# imx6_ctrl_i2c1.net
KiCad netlist of a schematic drawn in Altium Designer
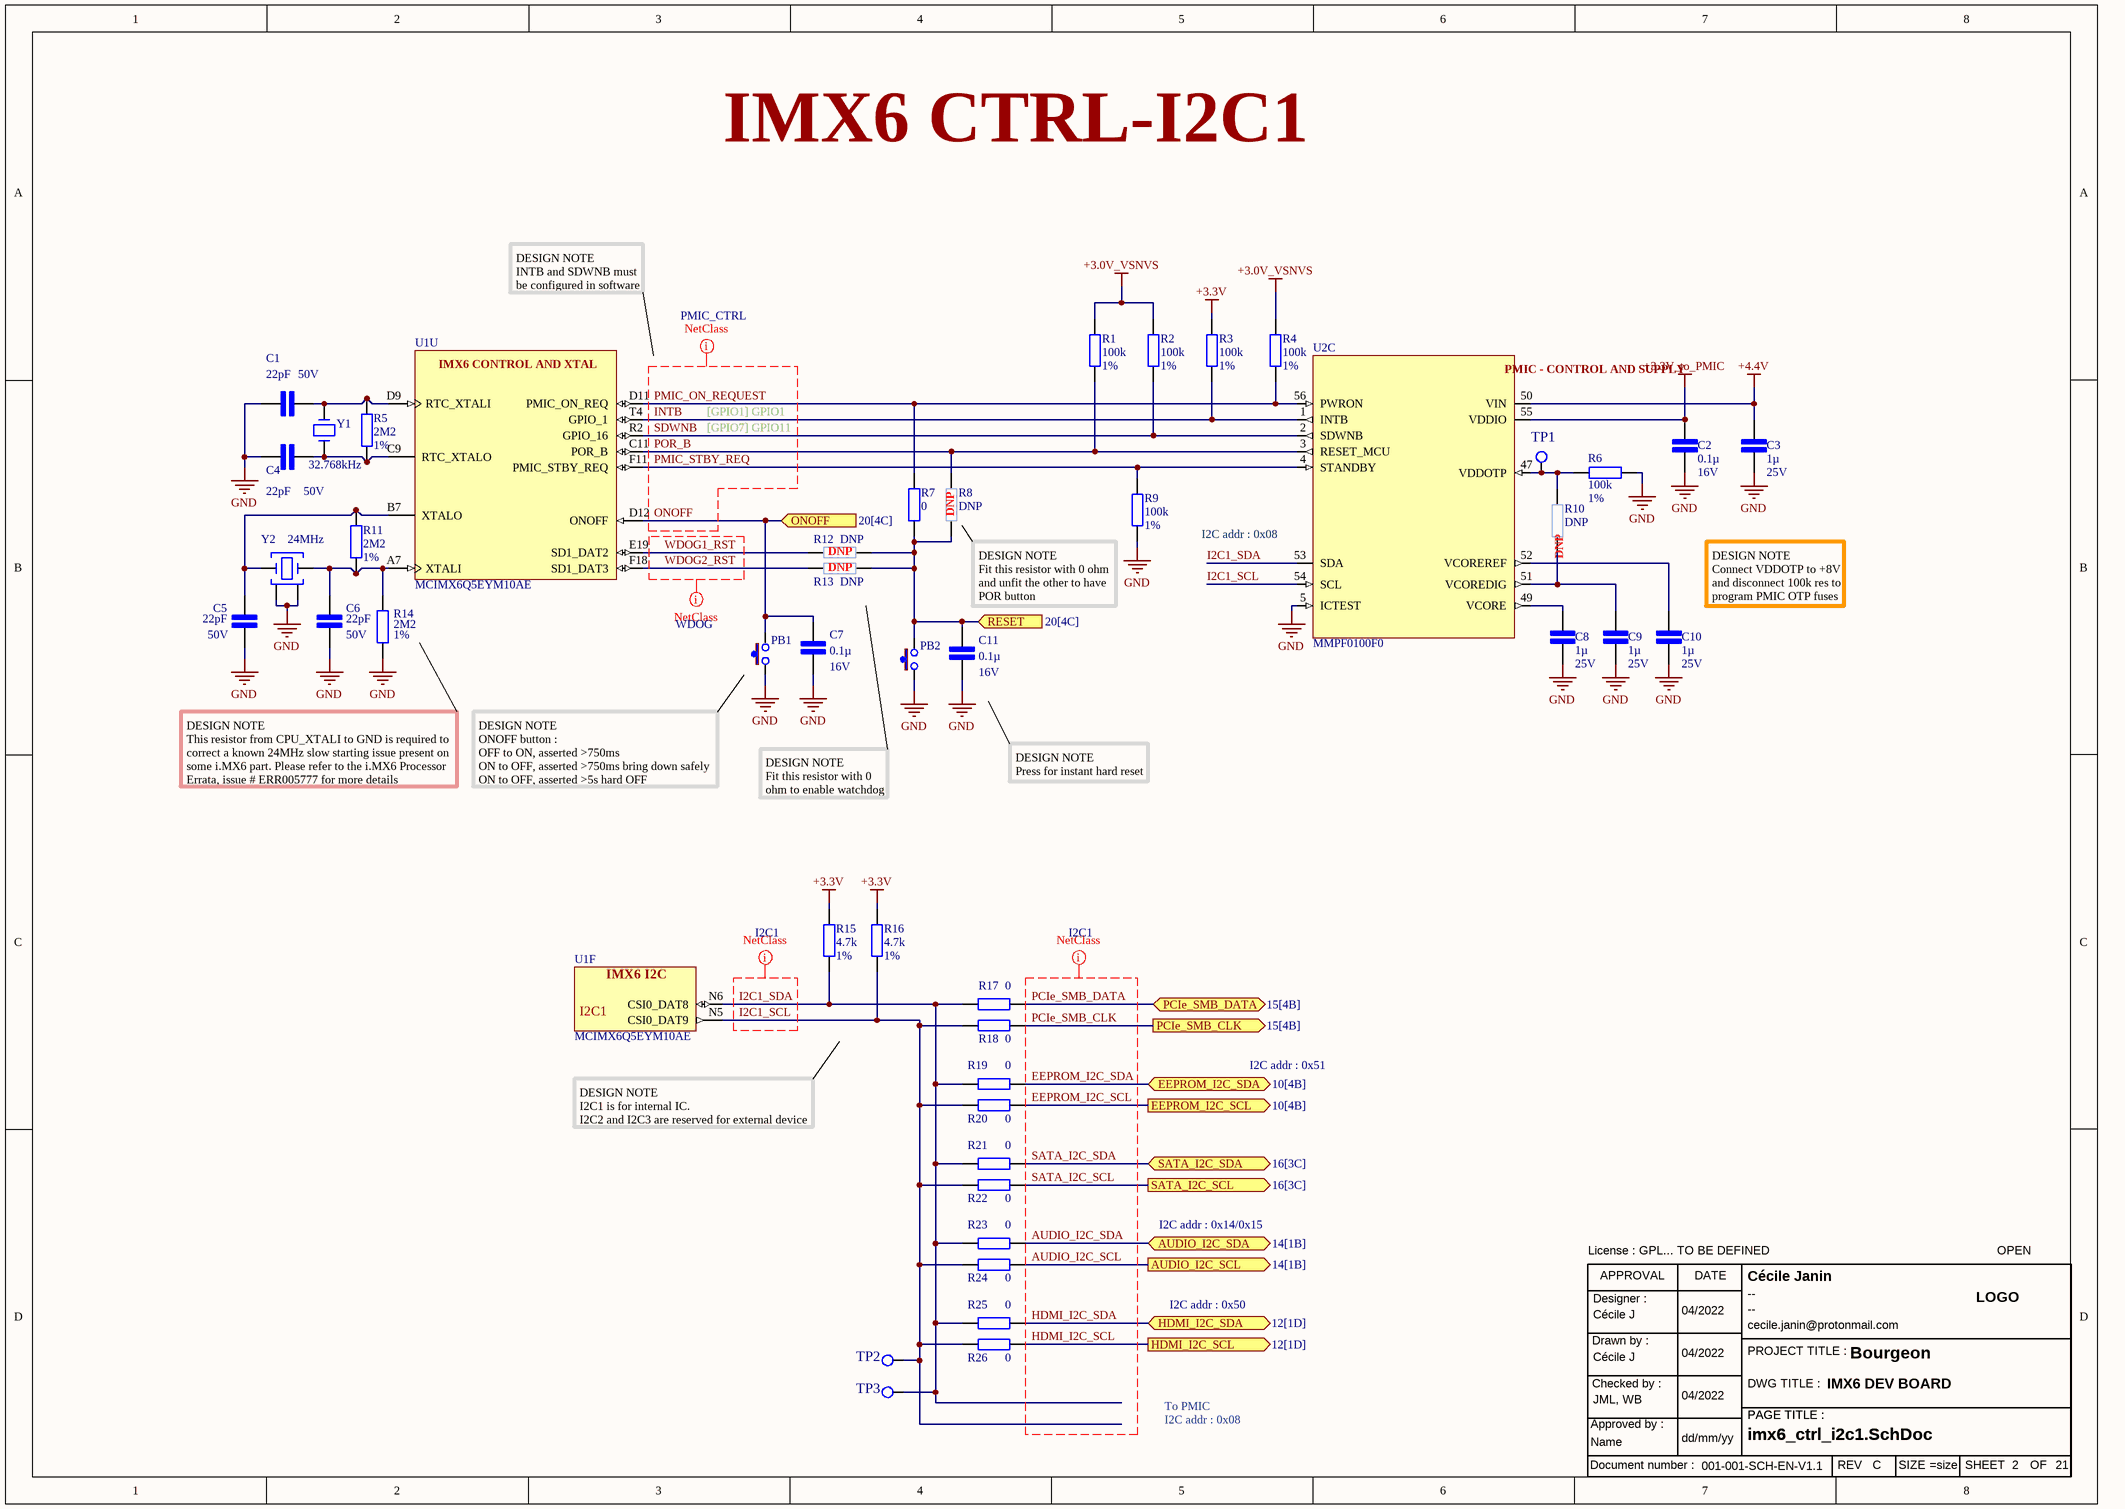
[diagram p0: imx6_ctrl_i2c1.SchDoc]

(export (version "E")
  (design (tool "Eeschema 10.0.6"))
  (components
    (comp (ref "C1")
      (value "22pF")
      (footprint "Cap cer 0402/1005")
      (description "cap cer 22pF 50V 5% NP0 0402")
      (fields (field (name "TENSION DU DIÉLECTRIQUE") "50V"))
      (libsource (lib "First Board IMX6") (part "cap 22pF 50V"))
    )
    (comp (ref "C2")
      (value "0.1µ")
      (footprint "Cap cer 0402/1005")
      (description "cap solid electrolyte 0.1µ 6.3V 10%")
      (fields (field (name "TENSION DU DIÉLECTRIQUE") "16V"))
      (libsource (lib "") (part "cap 0.1µ 16V_1"))
    )
    (comp (ref "C3")
      (value "1µ")
      (footprint "Cap cer 0402/1005")
      (description "cap cer 1µ 25V 10% X5R 0402")
      (fields (field (name "TENSION DU DIÉLECTRIQUE") "25V"))
      (libsource (lib "First Board IMX6") (part "cap 1µ 25V"))
    )
    (comp (ref "C4")
      (value "22pF")
      (footprint "Cap cer 0402/1005")
      (description "cap cer 22pF 50V 5% NP0 0402")
      (fields (field (name "TENSION DU DIÉLECTRIQUE") "50V"))
      (libsource (lib "First Board IMX6") (part "cap 22pF 50V"))
    )
    (comp (ref "C5")
      (value "22pF")
      (footprint "Cap cer 0402/1005")
      (description "cap cer 22pF 50V 5% NP0 0402")
      (fields (field (name "TENSION DU DIÉLECTRIQUE") "50V"))
      (libsource (lib "") (part "cap 22pF 50V_1"))
    )
    (comp (ref "C6")
      (value "22pF")
      (footprint "Cap cer 0402/1005")
      (description "cap cer 22pF 50V 5% NP0 0402")
      (fields (field (name "TENSION DU DIÉLECTRIQUE") "50V"))
      (libsource (lib "") (part "cap 22pF 50V_1"))
    )
    (comp (ref "C7")
      (value "0.1µ")
      (footprint "Cap cer 0402/1005")
      (description "cap solid electrolyte 0.1µ 6.3V 10%")
      (fields (field (name "TENSION DU DIÉLECTRIQUE") "16V"))
      (libsource (lib "First Board IMX6") (part "cap 0.1µ 16V"))
    )
    (comp (ref "C8")
      (value "1µ")
      (footprint "Cap cer 0402/1005")
      (description "cap cer 1µ 25V 10% X5R 0402")
      (fields (field (name "TENSION DU DIÉLECTRIQUE") "25V"))
      (libsource (lib "First Board IMX6") (part "cap 1µ 25V"))
    )
    (comp (ref "C9")
      (value "1µ")
      (footprint "Cap cer 0402/1005")
      (description "cap cer 1µ 25V 10% X5R 0402")
      (fields (field (name "TENSION DU DIÉLECTRIQUE") "25V"))
      (libsource (lib "First Board IMX6") (part "cap 1µ 25V"))
    )
    (comp (ref "C10")
      (value "1µ")
      (footprint "Cap cer 0402/1005")
      (description "cap cer 1µ 25V 10% X5R 0402")
      (fields (field (name "TENSION DU DIÉLECTRIQUE") "25V"))
      (libsource (lib "First Board IMX6") (part "cap 1µ 25V"))
    )
    (comp (ref "C11")
      (value "0.1µ")
      (footprint "Cap cer 0402/1005")
      (description "cap solid electrolyte 0.1µ 6.3V 10%")
      (fields (field (name "TENSION DU DIÉLECTRIQUE") "16V"))
      (libsource (lib "First Board IMX6") (part "cap 0.1µ 16V"))
    )
    (comp (ref "PB1")
      (value "pb_434121025816")
      (footprint "pb_434121025816")
      (libsource (lib "First Board IMX6") (part "pb_434121025816"))
    )
    (comp (ref "PB2")
      (value "pb_434121025816")
      (footprint "pb_434121025816")
      (libsource (lib "First Board IMX6") (part "pb_434121025816"))
    )
    (comp (ref "R1")
      (value "100k")
      (footprint "Res 0402/1005")
      (description "res 100k 1% 0402")
      (fields (field (name "POURCENTAGE") "1%"))
      (libsource (lib "First Board IMX6") (part "res 100k 1%"))
    )
    (comp (ref "R2")
      (value "100k")
      (footprint "Res 0402/1005")
      (description "res 100k 1% 0402")
      (fields (field (name "POURCENTAGE") "1%"))
      (libsource (lib "First Board IMX6") (part "res 100k 1%"))
    )
    (comp (ref "R3")
      (value "100k")
      (footprint "Res 0402/1005")
      (description "res 100k 1% 0402")
      (fields (field (name "POURCENTAGE") "1%"))
      (libsource (lib "First Board IMX6") (part "res 100k 1%"))
    )
    (comp (ref "R4")
      (value "100k")
      (footprint "Res 0402/1005")
      (description "res 100k 1% 0402")
      (fields (field (name "POURCENTAGE") "1%"))
      (libsource (lib "First Board IMX6") (part "res 100k 1%"))
    )
    (comp (ref "R5")
      (value "2M2")
      (footprint "Res 0402/1005")
      (description "res 2M2 1% 0402")
      (fields (field (name "POURCENTAGE") "1%"))
      (libsource (lib "First Board IMX6") (part "res 2M2 1%"))
    )
    (comp (ref "R6")
      (value "100k")
      (footprint "Res 0402/1005")
      (description "res 100k 1% 0402")
      (fields (field (name "POURCENTAGE") "1%"))
      (libsource (lib "First Board IMX6") (part "res 100k 1%"))
    )
    (comp (ref "R7")
      (value "0")
      (footprint "Res 0603/1603")
      (description "res 0603")
      (libsource (lib "First Board IMX6") (part "res 0Ohm"))
    )
    (comp (ref "R8")
      (value "DNP")
      (footprint "Res 0603/1603")
      (description "res DNP 0603")
      (libsource (lib "First Board IMX6") (part "res DNP 0603"))
    )
    (comp (ref "R9")
      (value "100k")
      (footprint "Res 0402/1005")
      (description "res 100k 1% 0402")
      (fields (field (name "POURCENTAGE") "1%"))
      (libsource (lib "First Board IMX6") (part "res 100k 1%"))
    )
    (comp (ref "R10")
      (value "DNP")
      (footprint "Res 0402/1005")
      (description "res DNP 0402")
      (libsource (lib "First Board IMX6") (part "res DNP"))
    )
    (comp (ref "R11")
      (value "2M2")
      (footprint "Res 0402/1005")
      (description "res 2M2 1% 0402")
      (fields (field (name "POURCENTAGE") "1%"))
      (libsource (lib "First Board IMX6") (part "res 2M2 1%"))
    )
    (comp (ref "R12")
      (value "DNP")
      (footprint "Res 0603/1603")
      (description "res DNP 0603")
      (libsource (lib "First Board IMX6") (part "res DNP 0603"))
    )
    (comp (ref "R13")
      (value "DNP")
      (footprint "Res 0603/1603")
      (description "res DNP 0603")
      (libsource (lib "First Board IMX6") (part "res DNP 0603"))
    )
    (comp (ref "R14")
      (value "2M2")
      (footprint "Res 0402/1005")
      (description "res 2M2 1% 0402")
      (fields (field (name "POURCENTAGE") "1%"))
      (libsource (lib "First Board IMX6") (part "res 2M2 1%"))
    )
    (comp (ref "R15")
      (value "4.7k")
      (footprint "Res 0402/1005")
      (description "res 4.7k 1% 0402")
      (fields (field (name "POURCENTAGE") "1%"))
      (libsource (lib "First Board IMX6") (part "res 4.7k 1%"))
    )
    (comp (ref "R16")
      (value "4.7k")
      (footprint "Res 0402/1005")
      (description "res 4.7k 1% 0402")
      (fields (field (name "POURCENTAGE") "1%"))
      (libsource (lib "First Board IMX6") (part "res 4.7k 1%"))
    )
    (comp (ref "R17")
      (value "0")
      (footprint "Res 0603/1603")
      (description "res 0603")
      (libsource (lib "First Board IMX6") (part "res 0Ohm"))
    )
    (comp (ref "R18")
      (value "0")
      (footprint "Res 0603/1603")
      (description "res 0603")
      (libsource (lib "First Board IMX6") (part "res 0Ohm"))
    )
    (comp (ref "R19")
      (value "0")
      (footprint "Res 0603/1603")
      (description "res 0603")
      (libsource (lib "First Board IMX6") (part "res 0Ohm"))
    )
    (comp (ref "R20")
      (value "0")
      (footprint "Res 0603/1603")
      (description "res 0603")
      (libsource (lib "First Board IMX6") (part "res 0Ohm"))
    )
    (comp (ref "R21")
      (value "0")
      (footprint "Res 0603/1603")
      (description "res 0603")
      (libsource (lib "First Board IMX6") (part "res 0Ohm"))
    )
    (comp (ref "R22")
      (value "0")
      (footprint "Res 0603/1603")
      (description "res 0603")
      (libsource (lib "First Board IMX6") (part "res 0Ohm"))
    )
    (comp (ref "R23")
      (value "0")
      (footprint "Res 0603/1603")
      (description "res 0603")
      (libsource (lib "First Board IMX6") (part "res 0Ohm"))
    )
    (comp (ref "R24")
      (value "0")
      (footprint "Res 0603/1603")
      (description "res 0603")
      (libsource (lib "First Board IMX6") (part "res 0Ohm"))
    )
    (comp (ref "R25")
      (value "0")
      (footprint "Res 0603/1603")
      (description "res 0603")
      (libsource (lib "First Board IMX6") (part "res 0Ohm"))
    )
    (comp (ref "R26")
      (value "0")
      (footprint "Res 0603/1603")
      (description "res 0603")
      (libsource (lib "First Board IMX6") (part "res 0Ohm"))
    )
    (comp (ref "TB3")
      (value "Title bloc ANSI modified")
      (libsource (lib "First Board IMX6") (part "Title bloc ANSI"))
    )
    (comp (ref "TP1")
      (value "Test Point")
      (footprint "testpoint 1mm")
      (description "Test point 1mm diameter")
      (libsource (lib "First Board IMX6") (part "Test Point"))
    )
    (comp (ref "TP2")
      (value "Test Point")
      (footprint "testpoint 1mm")
      (description "Test point 1mm diameter")
      (libsource (lib "First Board IMX6") (part "Test Point"))
    )
    (comp (ref "TP3")
      (value "Test Point")
      (footprint "testpoint 1mm")
      (description "Test point 1mm diameter")
      (libsource (lib "First Board IMX6") (part "Test Point"))
    )
    (comp (ref "U1")
      (value "MCIMX6Q5EYM10AE")
      (footprint "FRES-2197-01")
      (fields
        (field (name "PARTNUMBER") "MCIMX6Q5EYM10ACR")
        (field (name "MANUFACTURER") "Freescale Semiconductor")
      )
      (libsource (lib "First Board IMX6") (part "IMX6Q5EYM10AE"))
    )
    (comp (ref "U2")
      (value "MMPF0100F0")
      (footprint "MMPF0100")
      (description "PMIC")
      (libsource (lib "First Board IMX6") (part "IC MMPF0100"))
    )
    (comp (ref "Y1")
      (value "32.768kHz")
      (footprint "IQXC-25")
      (description "WE-XTAL, 25MHz, +/-10ppm 830062558")
      (libsource (lib "First Board IMX6") (part "XTAL 32.768kHz"))
    )
    (comp (ref "Y2")
      (value "24MHz")
      (footprint "IQXC-42")
      (description "WE-XTAL 24MHz, +/-10ppm\r\n830108212309")
      (fields
        (field (name "MANUFACTURER PART NUMBER") "830108212309")
        (field (name "MANUFACTURER") "Wurth Elektronik")
      )
      (libsource (lib "First Board IMX6") (part "XTAL 24MHz"))
    )
  )
  (nets
    (net (code "1") (name "+3.0V_VSNVS") (class "Default")
      (node (ref "R1") (pin "2") (pintype "passive"))
      (node (ref "R2") (pin "2") (pintype "passive"))
      (node (ref "R4") (pin "2") (pintype "passive"))
    )
    (net (code "2") (name "+3.3V") (class "Default")
      (node (ref "R15") (pin "2") (pintype "passive"))
      (node (ref "R16") (pin "2") (pintype "passive"))
      (node (ref "R3") (pin "2") (pintype "passive"))
    )
    (net (code "3") (name "+3.3V_to_PMIC") (class "Default")
      (node (ref "C2") (pin "1") (pinfunction "3_1") (pintype "passive"))
      (node (ref "U2") (pin "55") (pinfunction "VDDIO_55") (pintype "power_in"))
    )
    (net (code "4") (name "+4.4V") (class "Default")
      (node (ref "C3") (pin "1") (pinfunction "3_1") (pintype "passive"))
      (node (ref "U2") (pin "50") (pinfunction "VIN_50") (pintype "power_in"))
    )
    (net (code "5") (name "/AUDIO_I2C_SCL") (class "Default")
      (node (ref "R24") (pin "2") (pintype "passive"))
    )
    (net (code "6") (name "/AUDIO_I2C_SDA") (class "Default")
      (node (ref "R23") (pin "2") (pintype "passive"))
    )
    (net (code "7") (name "/EEPROM_I2C_SCL") (class "Default")
      (node (ref "R20") (pin "2") (pintype "passive"))
    )
    (net (code "8") (name "/EEPROM_I2C_SDA") (class "Default")
      (node (ref "R19") (pin "2") (pintype "passive"))
    )
    (net (code "9") (name "/HDMI_I2C_SCL") (class "Default") (node (ref "R26") (pin "2") (pintype "passive")))
    (net (code "10") (name "/HDMI_I2C_SDA") (class "Default")
      (node (ref "R25") (pin "2") (pintype "passive"))
    )
    (net (code "11") (name "/I2C1_SCL") (class "Default")
      (node (ref "R16") (pin "1") (pintype "passive"))
      (node (ref "R18") (pin "1") (pintype "passive"))
      (node (ref "R20") (pin "1") (pintype "passive"))
      (node (ref "R22") (pin "1") (pintype "passive"))
      (node (ref "R24") (pin "1") (pintype "passive"))
      (node (ref "R26") (pin "1") (pintype "passive"))
      (node (ref "TP2") (pin "1") (pinfunction "tp_1") (pintype "passive"))
      (node (ref "U1") (pin "N5") (pinfunction "CSI0_DAT9_N5") (pintype "output"))
      (node (ref "U2") (pin "54") (pinfunction "SCL_54") (pintype "input"))
    )
    (net (code "12") (name "/I2C1_SDA") (class "Default")
      (node (ref "R15") (pin "1") (pintype "passive"))
      (node (ref "R17") (pin "1") (pintype "passive"))
      (node (ref "R19") (pin "1") (pintype "passive"))
      (node (ref "R21") (pin "1") (pintype "passive"))
      (node (ref "R23") (pin "1") (pintype "passive"))
      (node (ref "R25") (pin "1") (pintype "passive"))
      (node (ref "TP3") (pin "1") (pinfunction "tp_1") (pintype "passive"))
      (node (ref "U1") (pin "N6") (pinfunction "CSI0_DAT8_N6") (pintype "bidirectional"))
      (node (ref "U2") (pin "53") (pinfunction "SDA_53") (pintype "bidirectional"))
    )
    (net (code "13") (name "/INTB") (class "Default")
      (node (ref "R3") (pin "1") (pintype "passive"))
      (node (ref "U1") (pin "T4") (pinfunction "GPIO_1_T4") (pintype "bidirectional"))
      (node (ref "U2") (pin "1") (pinfunction "INTB_1") (pintype "output"))
    )
    (net (code "14") (name "/ONOFF") (class "Default")
      (node (ref "C7") (pin "1") (pinfunction "3_1") (pintype "passive"))
      (node (ref "PB1") (pin "2") (pinfunction "2_2") (pintype "passive"))
      (node (ref "U1") (pin "D12") (pinfunction "ONOFF_D12") (pintype "input"))
    )
    (net (code "15") (name "/PCIe_SMB_CLK") (class "Default")
      (node (ref "R18") (pin "2") (pintype "passive"))
    )
    (net (code "16") (name "/PCIe_SMB_DATA") (class "Default")
      (node (ref "R17") (pin "2") (pintype "passive"))
    )
    (net (code "17") (name "/PMIC_ON_REQUEST") (class "Default")
      (node (ref "R4") (pin "1") (pintype "passive"))
      (node (ref "R7") (pin "2") (pintype "passive"))
      (node (ref "U1") (pin "D11") (pinfunction "PMIC_ON_REQ_D11") (pintype "bidirectional"))
      (node (ref "U2") (pin "56") (pinfunction "PWRON_56") (pintype "input"))
    )
    (net (code "18") (name "/PMIC_STBY_REQ") (class "Default")
      (node (ref "R9") (pin "2") (pintype "passive"))
      (node (ref "U1") (pin "F11") (pinfunction "PMIC_STBY_REQ_F11") (pintype "bidirectional"))
      (node (ref "U2") (pin "4") (pinfunction "STANDBY_4") (pintype "input"))
    )
    (net (code "19") (name "/POR_B") (class "Default")
      (node (ref "R1") (pin "1") (pintype "passive"))
      (node (ref "R8") (pin "2") (pintype "passive"))
      (node (ref "U1") (pin "C11") (pinfunction "POR_B_C11") (pintype "bidirectional"))
      (node (ref "U2") (pin "3") (pinfunction "RESET_MCU_3") (pintype "output"))
    )
    (net (code "20") (name "/RESET") (class "Default")
      (node (ref "C11") (pin "1") (pinfunction "3_1") (pintype "passive"))
      (node (ref "PB2") (pin "2") (pinfunction "2_2") (pintype "passive"))
      (node (ref "R12") (pin "2") (pintype "passive"))
      (node (ref "R13") (pin "2") (pintype "passive"))
      (node (ref "R7") (pin "1") (pintype "passive"))
      (node (ref "R8") (pin "1") (pintype "passive"))
    )
    (net (code "21") (name "/SATA_I2C_SCL") (class "Default")
      (node (ref "R22") (pin "2") (pintype "passive"))
    )
    (net (code "22") (name "/SATA_I2C_SDA") (class "Default")
      (node (ref "R21") (pin "2") (pintype "passive"))
    )
    (net (code "23") (name "/SDWNB") (class "Default")
      (node (ref "R2") (pin "1") (pintype "passive"))
      (node (ref "U1") (pin "R2") (pinfunction "GPIO_16_R2") (pintype "bidirectional"))
      (node (ref "U2") (pin "2") (pinfunction "SDWNB_2") (pintype "output"))
    )
    (net (code "24") (name "/WDOG1_RST") (class "Default")
      (node (ref "R12") (pin "1") (pintype "passive"))
      (node (ref "U1") (pin "E19") (pinfunction "SD1_DAT2_E19") (pintype "bidirectional"))
    )
    (net (code "25") (name "/WDOG2_RST") (class "Default")
      (node (ref "R13") (pin "1") (pintype "passive"))
      (node (ref "U1") (pin "F18") (pinfunction "SD1_DAT3_F18") (pintype "bidirectional"))
    )
    (net (code "26") (name "GND") (class "Default")
      (node (ref "C1") (pin "2") (pinfunction "4_2") (pintype "passive"))
      (node (ref "C10") (pin "2") (pinfunction "4_2") (pintype "passive"))
      (node (ref "C11") (pin "2") (pinfunction "4_2") (pintype "passive"))
      (node (ref "C2") (pin "2") (pinfunction "4_2") (pintype "passive"))
      (node (ref "C3") (pin "2") (pinfunction "4_2") (pintype "passive"))
      (node (ref "C4") (pin "2") (pinfunction "4_2") (pintype "passive"))
      (node (ref "C5") (pin "2") (pinfunction "4_2") (pintype "passive"))
      (node (ref "C6") (pin "2") (pinfunction "4_2") (pintype "passive"))
      (node (ref "C7") (pin "2") (pinfunction "4_2") (pintype "passive"))
      (node (ref "C8") (pin "2") (pinfunction "4_2") (pintype "passive"))
      (node (ref "C9") (pin "2") (pinfunction "4_2") (pintype "passive"))
      (node (ref "PB1") (pin "1") (pinfunction "1_1") (pintype "passive"))
      (node (ref "PB2") (pin "1") (pinfunction "1_1") (pintype "passive"))
      (node (ref "R14") (pin "1") (pintype "passive"))
      (node (ref "R6") (pin "1") (pintype "passive"))
      (node (ref "R9") (pin "1") (pintype "passive"))
      (node (ref "U2") (pin "5") (pinfunction "ICTEST_5") (pintype "input"))
      (node (ref "Y2") (pin "2") (pinfunction "GND_2") (pintype "passive"))
      (node (ref "Y2") (pin "4") (pinfunction "GND_4") (pintype "passive"))
    )
    (net (code "27") (name "Net-(C1-3)") (class "Default")
      (node (ref "C1") (pin "1") (pinfunction "3_1") (pintype "passive"))
      (node (ref "R5") (pin "2") (pintype "passive"))
      (node (ref "U1") (pin "D9") (pinfunction "RTC_XTALI_D9") (pintype "input"))
      (node (ref "Y1") (pin "2") (pinfunction "Crystal_2") (pintype "passive"))
    )
    (net (code "28") (name "Net-(C4-3)") (class "Default")
      (node (ref "C4") (pin "1") (pinfunction "3_1") (pintype "passive"))
      (node (ref "R5") (pin "1") (pintype "passive"))
      (node (ref "U1") (pin "C9") (pinfunction "RTC_XTALO_C9") (pintype "passive"))
      (node (ref "Y1") (pin "1") (pinfunction "Crystal_1") (pintype "passive"))
    )
    (net (code "29") (name "Net-(C5-3)") (class "Default")
      (node (ref "C5") (pin "1") (pinfunction "3_1") (pintype "passive"))
      (node (ref "R11") (pin "2") (pintype "passive"))
      (node (ref "U1") (pin "B7") (pinfunction "XTALO_B7") (pintype "passive"))
      (node (ref "Y2") (pin "1") (pinfunction "Crystal_1") (pintype "passive"))
    )
    (net (code "30") (name "Net-(C6-3)") (class "Default")
      (node (ref "C6") (pin "1") (pinfunction "3_1") (pintype "passive"))
      (node (ref "R11") (pin "1") (pintype "passive"))
      (node (ref "R14") (pin "2") (pintype "passive"))
      (node (ref "U1") (pin "A7") (pinfunction "XTALI_A7") (pintype "input"))
      (node (ref "Y2") (pin "3") (pinfunction "Crystal_3") (pintype "passive"))
    )
    (net (code "31") (name "Net-(C8-3)") (class "Default")
      (node (ref "C8") (pin "1") (pinfunction "3_1") (pintype "passive"))
      (node (ref "U2") (pin "49") (pinfunction "VCORE_49") (pintype "output"))
    )
    (net (code "32") (name "Net-(C9-3)") (class "Default")
      (node (ref "C9") (pin "1") (pinfunction "3_1") (pintype "passive"))
      (node (ref "R10") (pin "1") (pintype "passive"))
      (node (ref "U2") (pin "51") (pinfunction "VCOREDIG_51") (pintype "output"))
    )
    (net (code "33") (name "Net-(C10-3)") (class "Default")
      (node (ref "C10") (pin "1") (pinfunction "3_1") (pintype "passive"))
      (node (ref "U2") (pin "52") (pinfunction "VCOREREF_52") (pintype "output"))
    )
    (net (code "34") (name "Net-(TP1-tp)") (class "Default")
      (node (ref "R10") (pin "2") (pintype "passive"))
      (node (ref "R6") (pin "2") (pintype "passive"))
      (node (ref "TP1") (pin "1") (pinfunction "tp_1") (pintype "passive"))
      (node (ref "U2") (pin "47") (pinfunction "VDDOTP_47") (pintype "input"))
    )
  )
)
